# mini-v1_8-seed.net
KiCad netlist of a schematic drawn in EAGLE
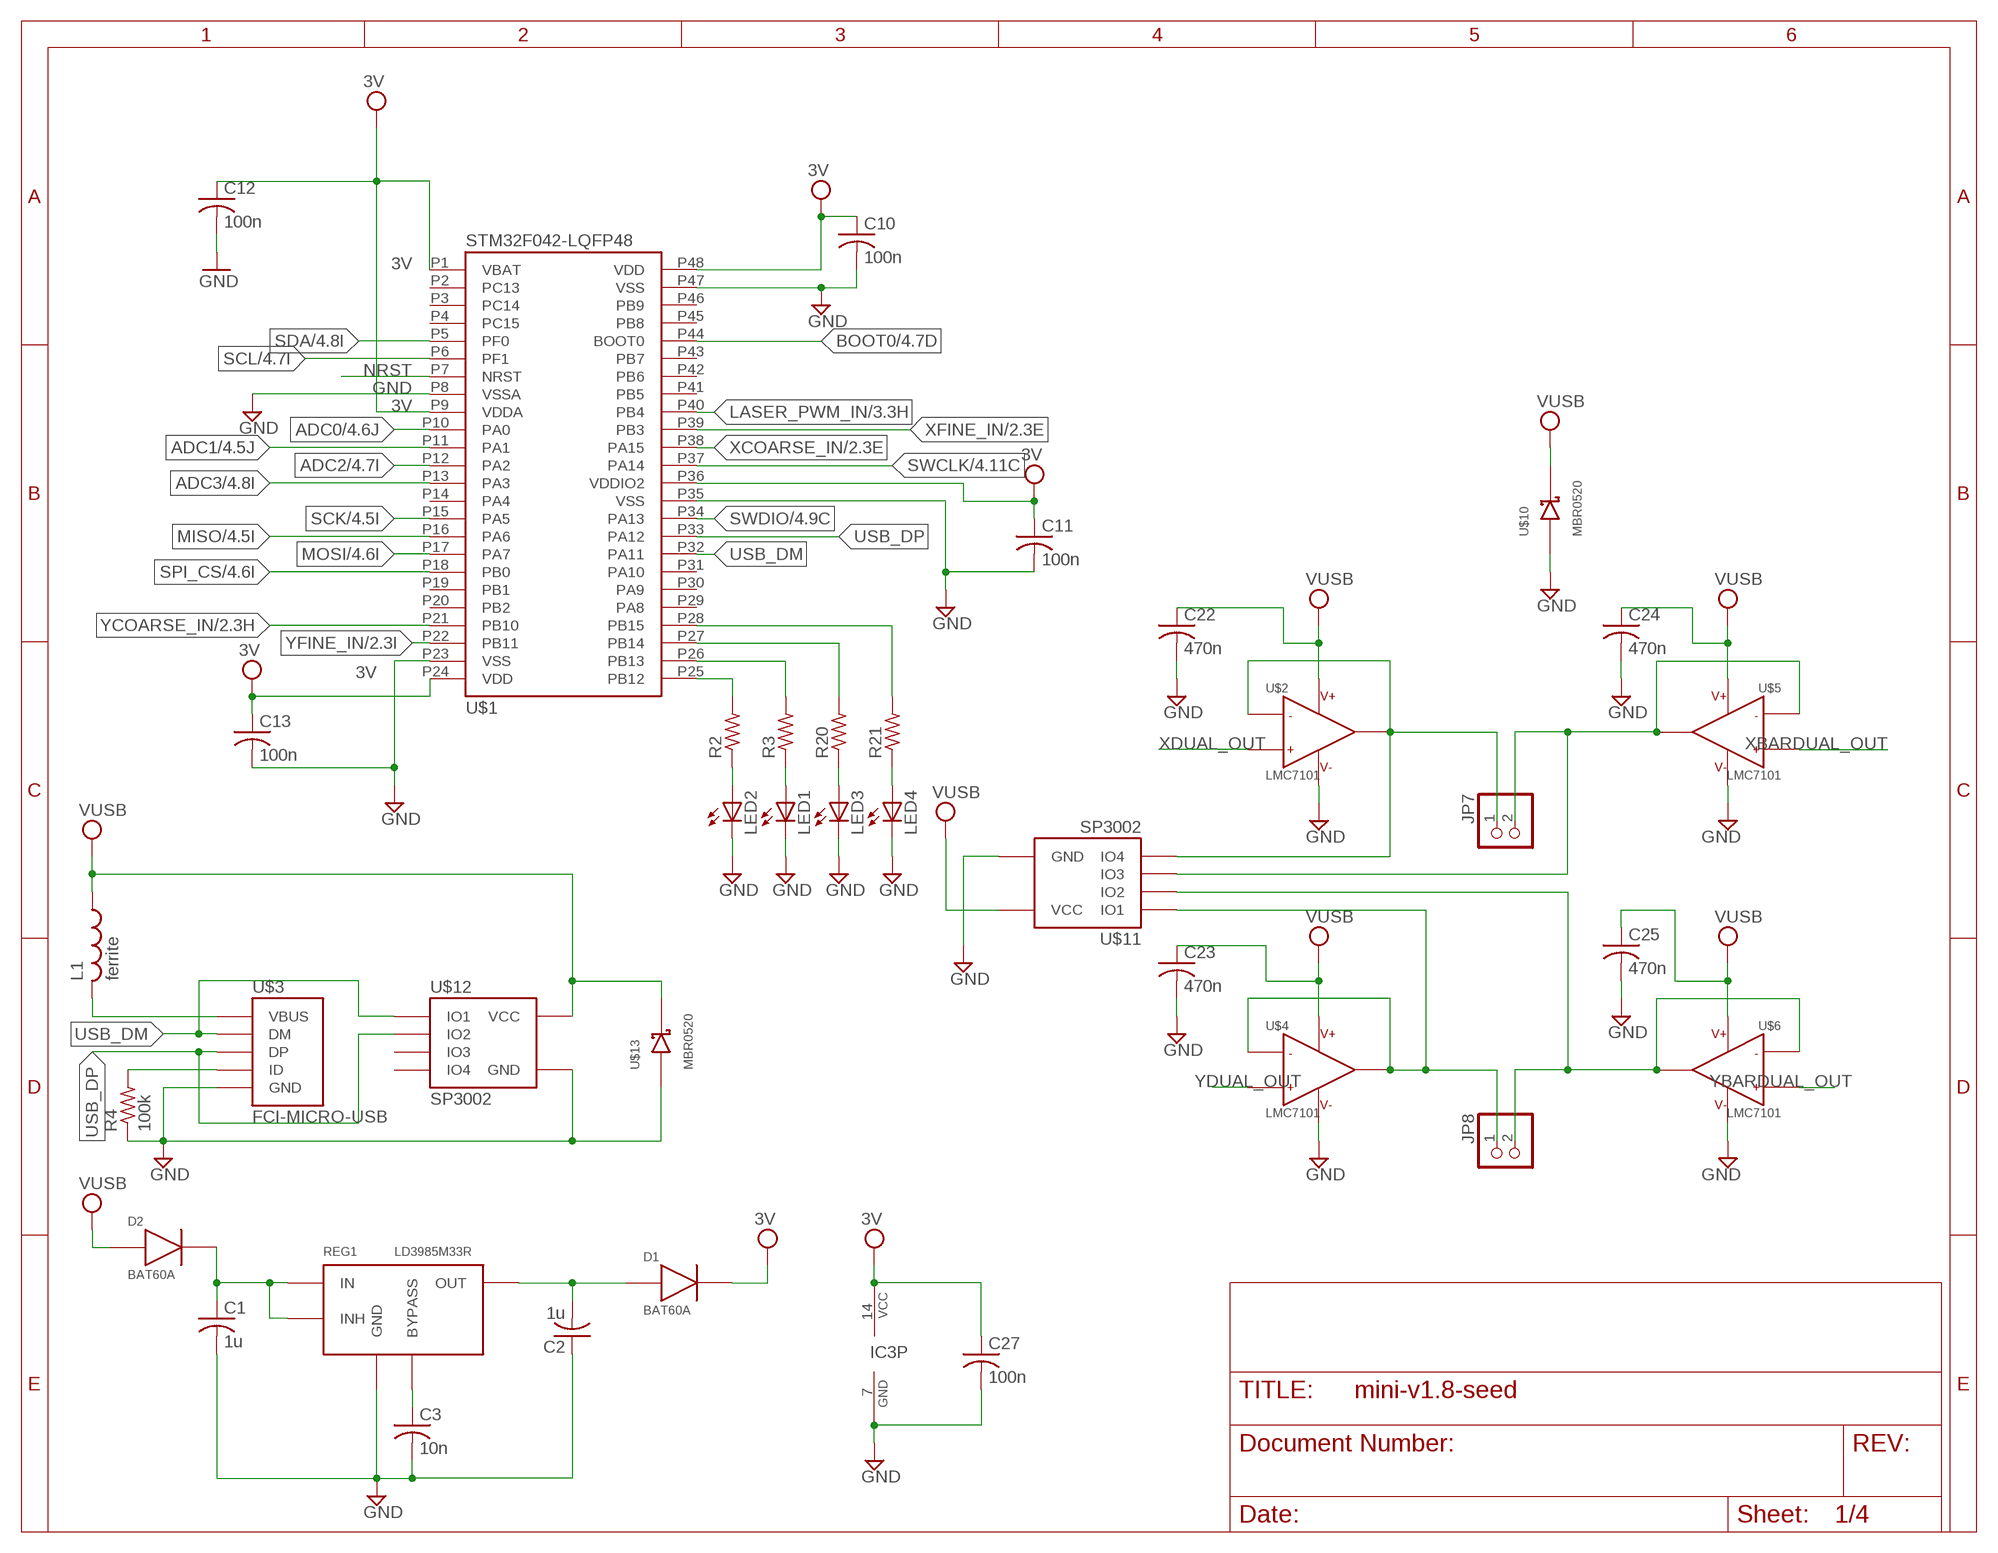
[diagram p0: schematic, sheet 1]
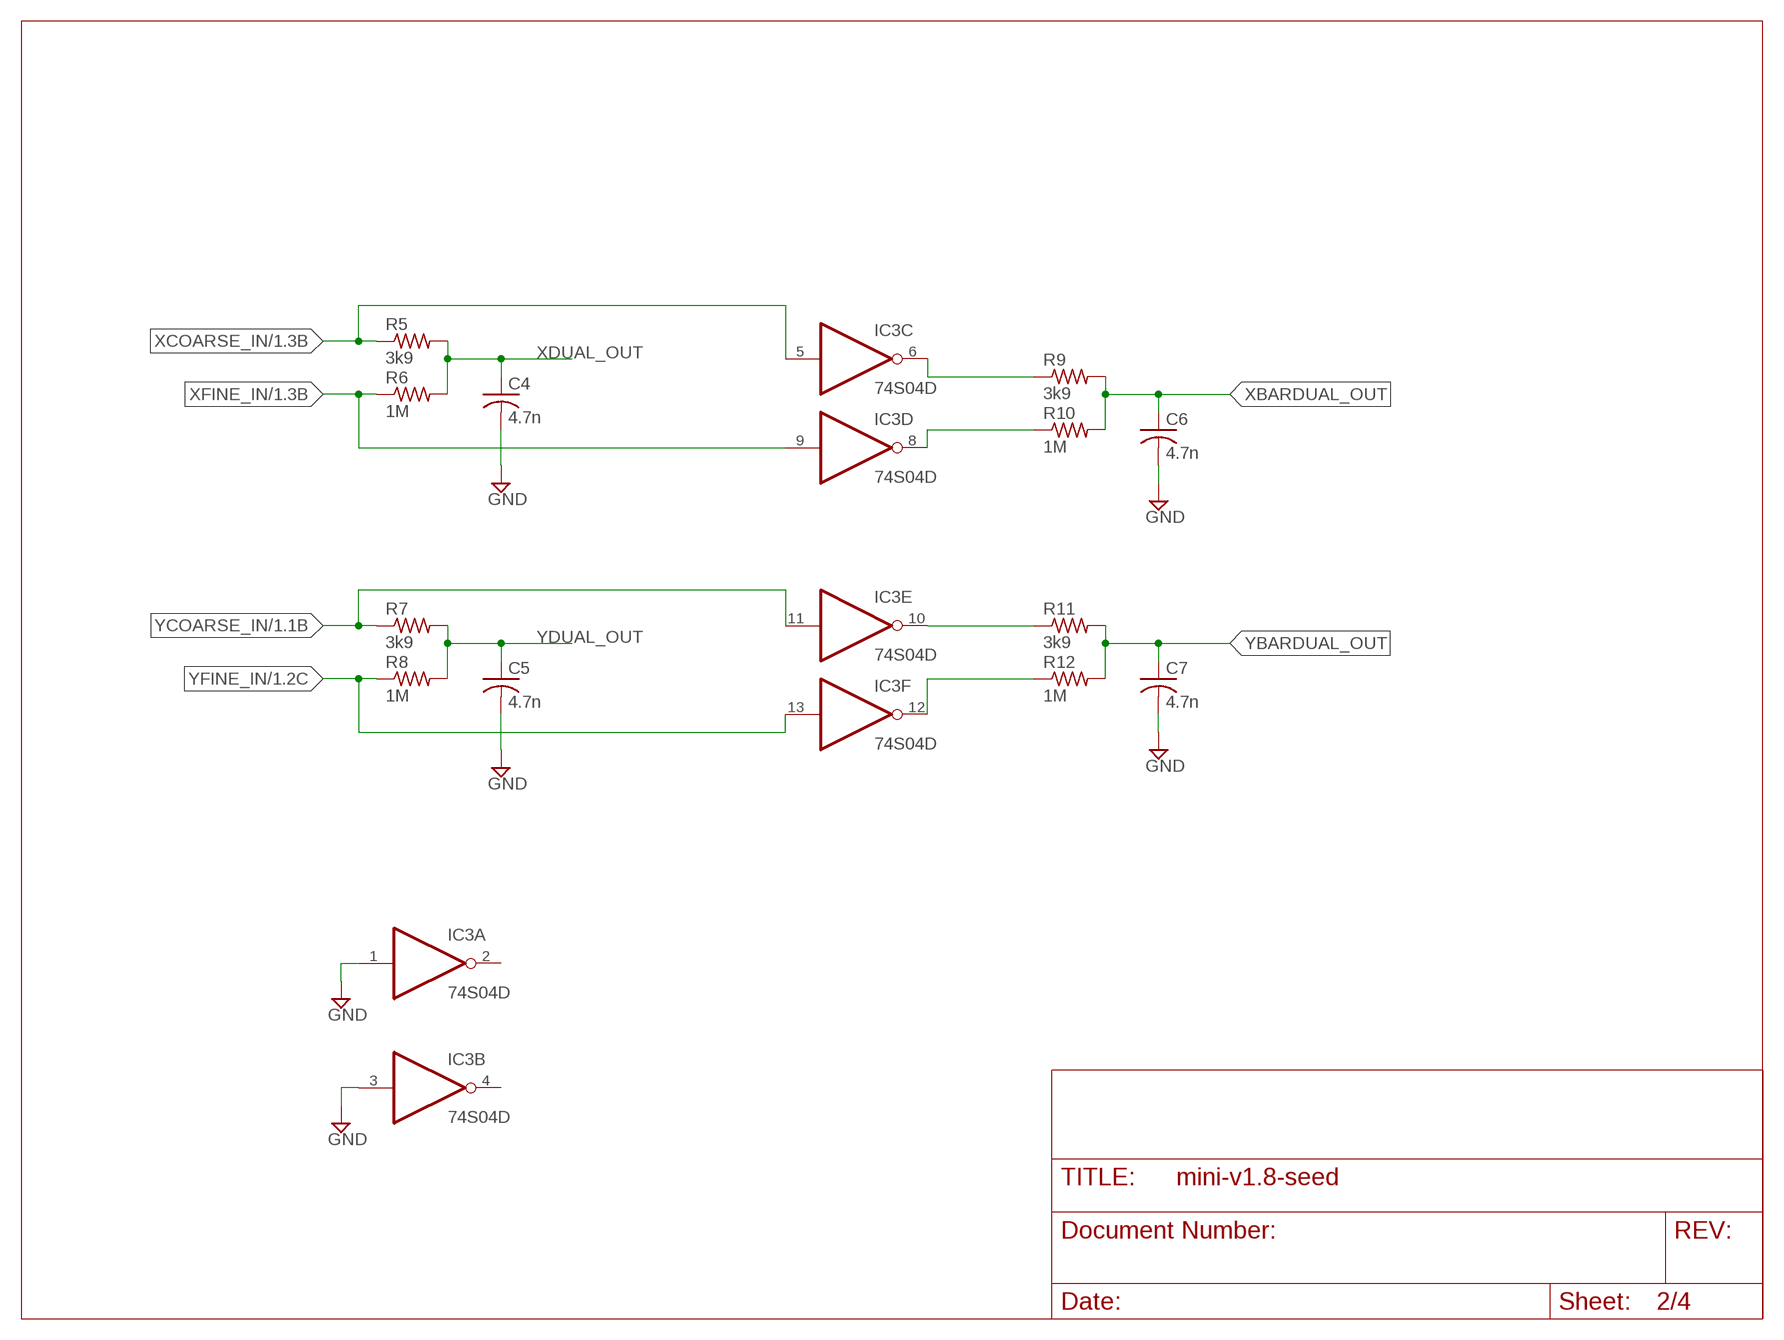
[diagram p1: schematic, sheet 2]
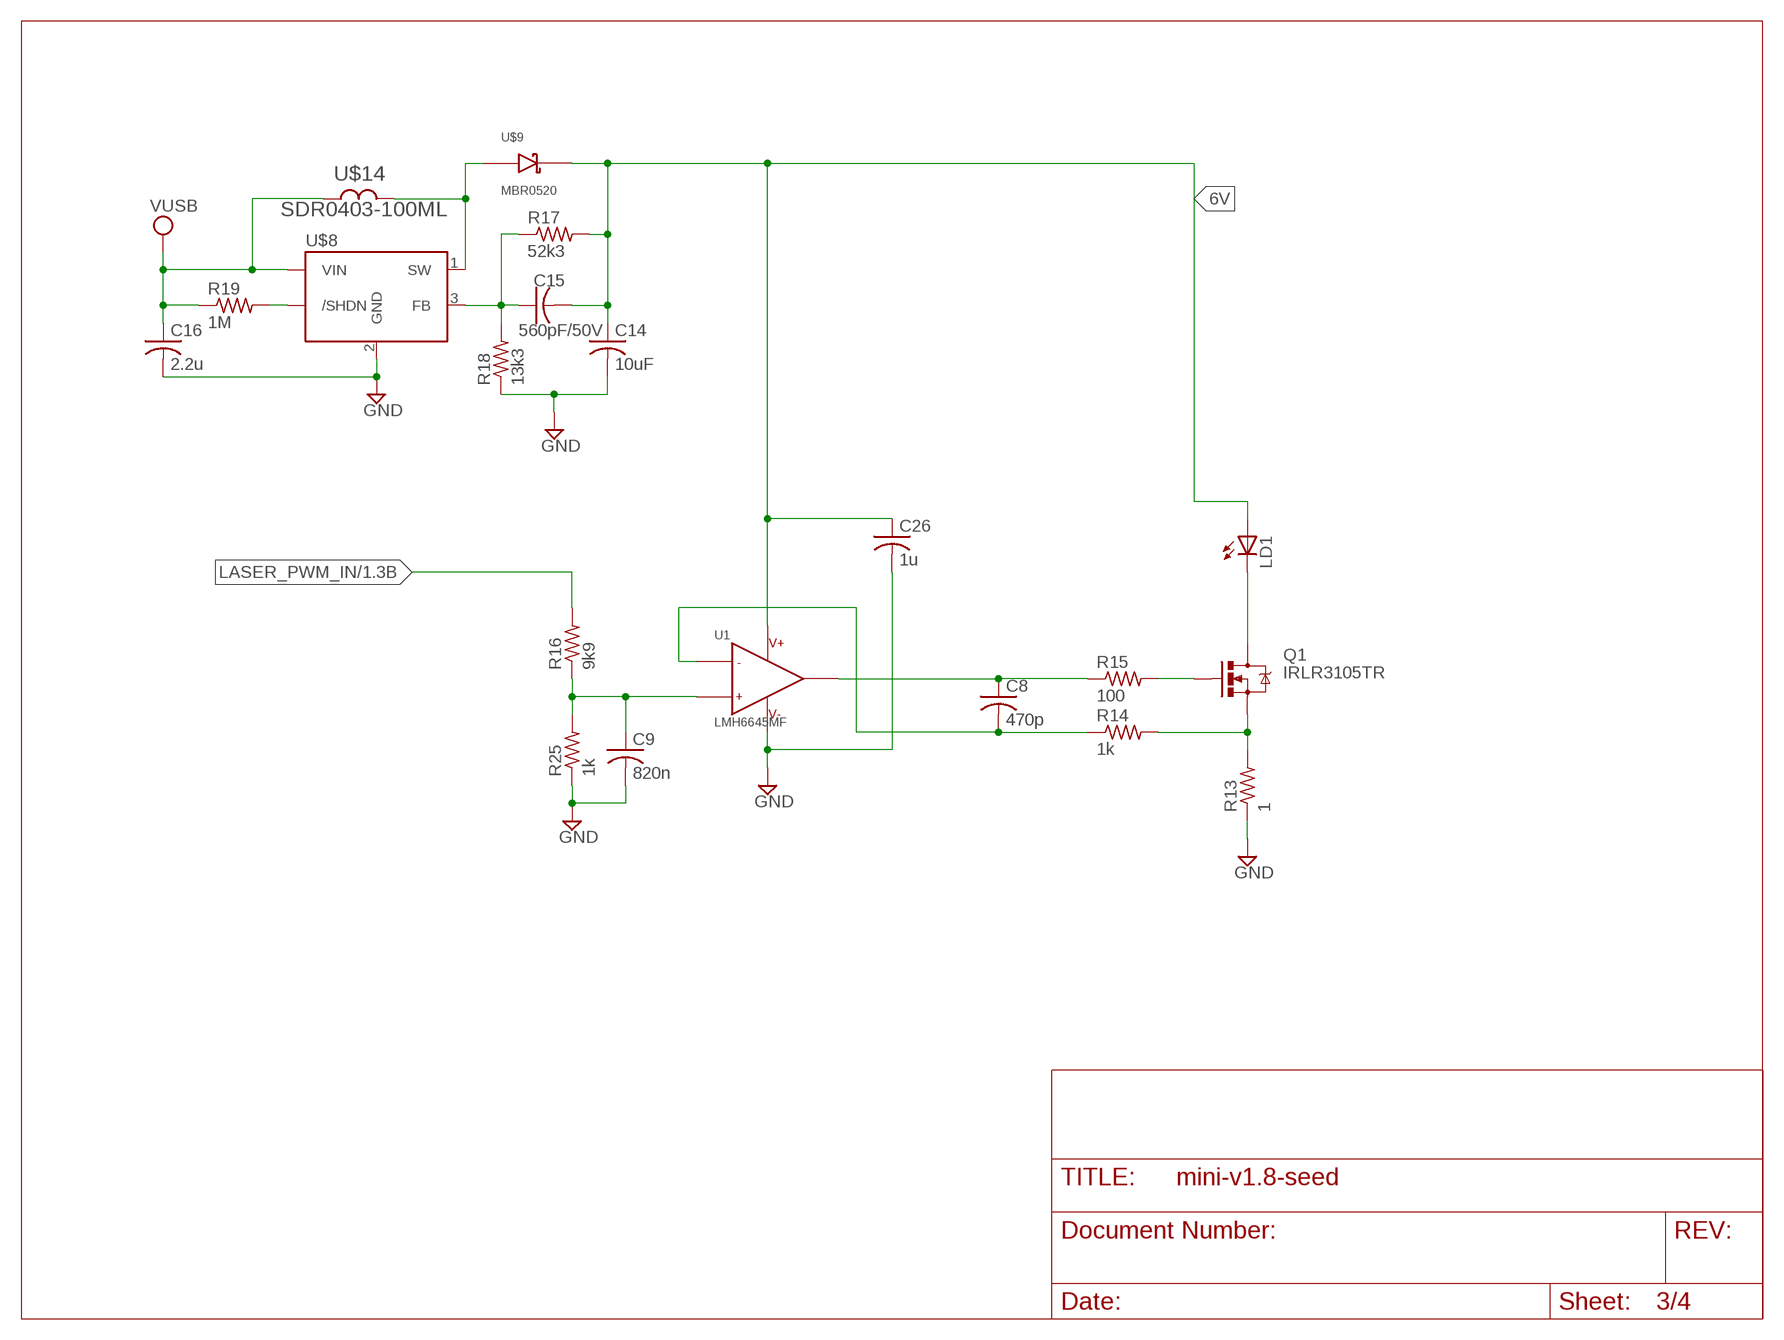
[diagram p2: schematic, sheet 3]
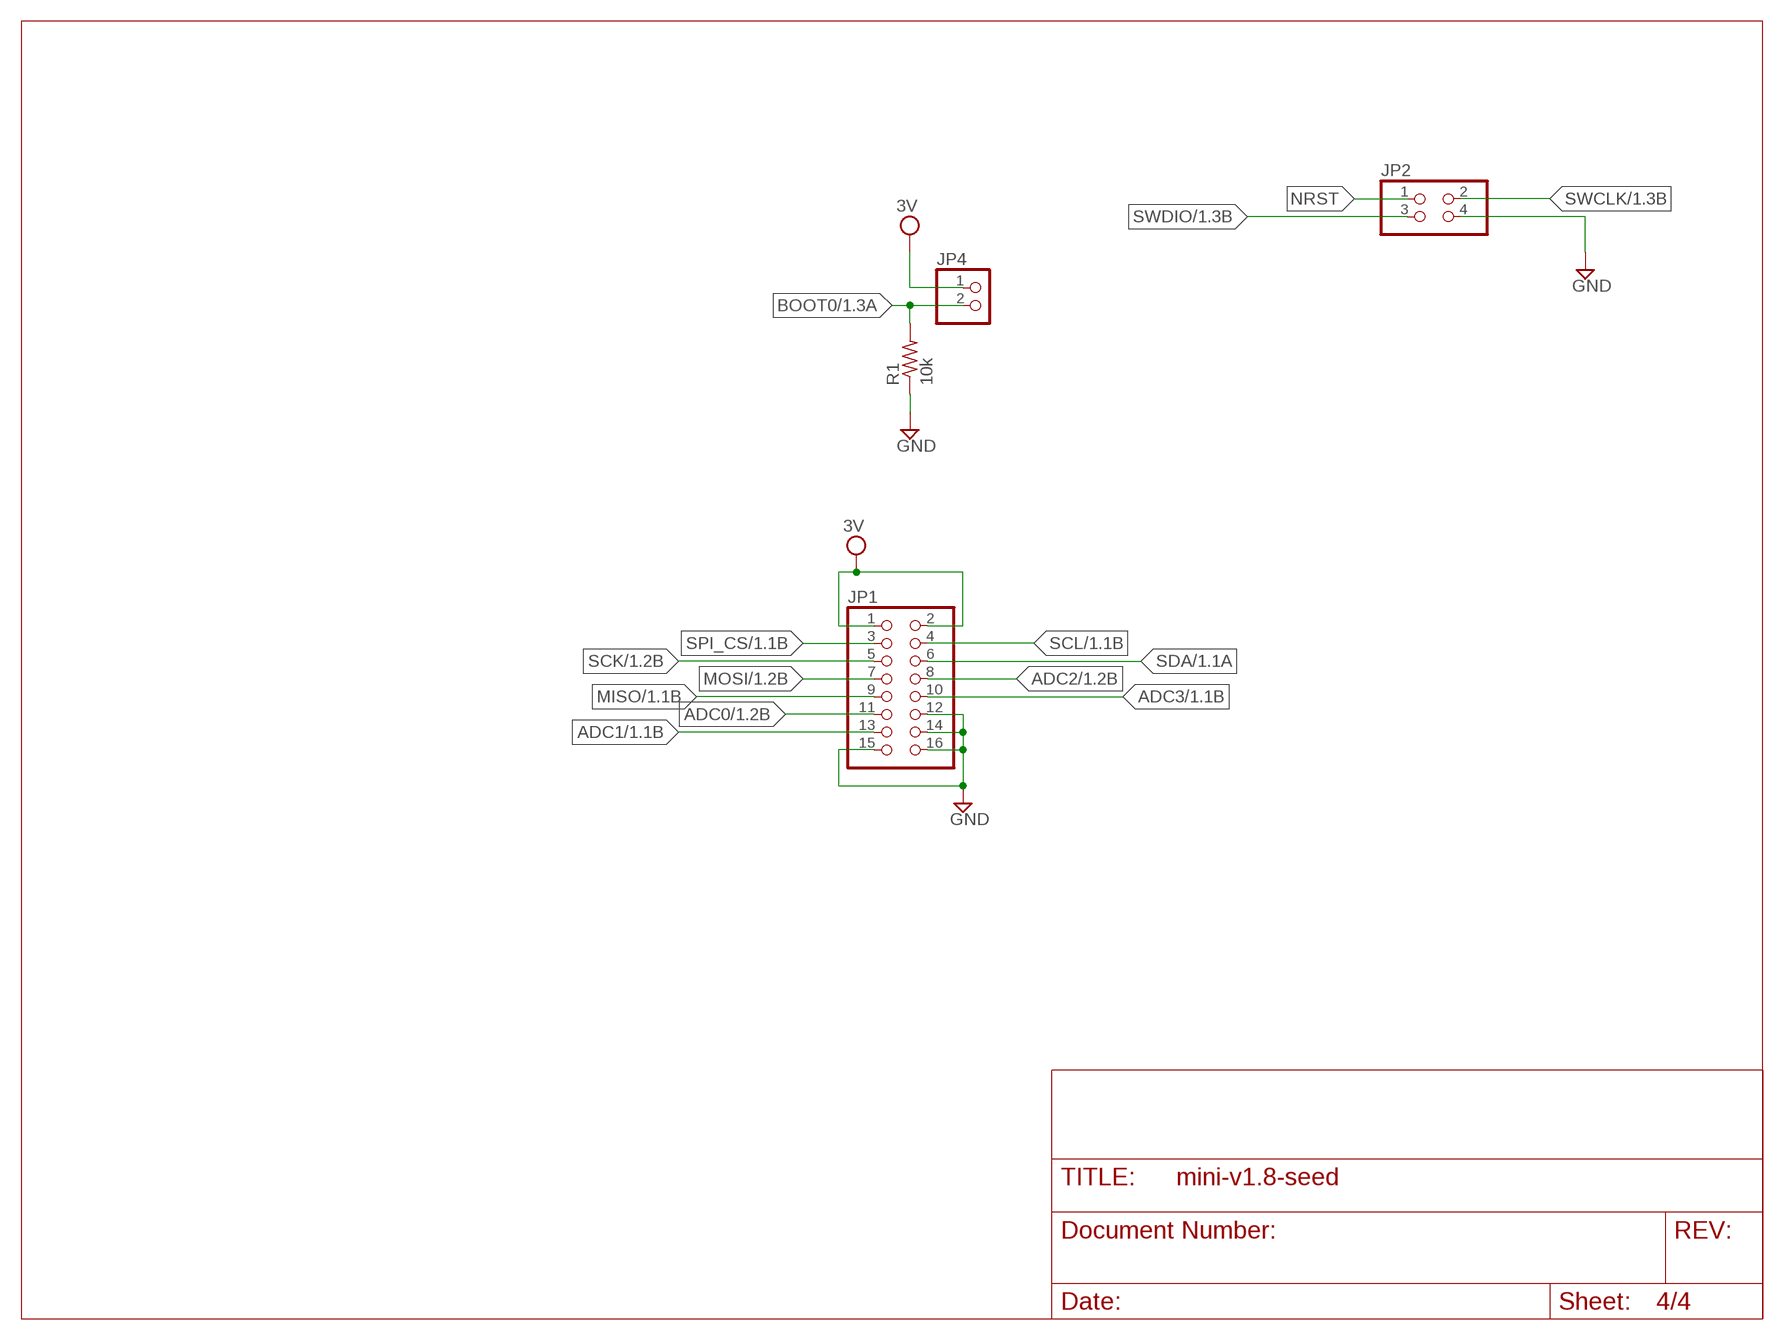
[diagram p3: schematic, sheet 4]

(export (version "E")
  (design (tool "Eeschema 10.0.6"))
  (components
    (comp (ref "C4")
      (value "4.7n")
      (footprint "eagle-import:C0603")
      (libsource (lib "eagle-import") (part "C-USC0603"))
    )
    (comp (ref "C5")
      (value "4.7n")
      (footprint "eagle-import:C0603")
      (libsource (lib "eagle-import") (part "C-USC0603"))
    )
    (comp (ref "C6")
      (value "4.7n")
      (footprint "eagle-import:C0603")
      (libsource (lib "eagle-import") (part "C-USC0603"))
    )
    (comp (ref "C7")
      (value "4.7n")
      (footprint "eagle-import:C0603")
      (libsource (lib "eagle-import") (part "C-USC0603"))
    )
    (comp (ref "IC3")
      (value "74S04D")
      (footprint "eagle-import:SO14")
      (libsource (lib "eagle-import") (part "7404DS"))
    )
    (comp (ref "R5")
      (value "3k9")
      (footprint "eagle-import:R0603")
      (libsource (lib "eagle-import") (part "R-US_R0603"))
    )
    (comp (ref "R6")
      (value "1M")
      (footprint "eagle-import:R0603")
      (libsource (lib "eagle-import") (part "R-US_R0603"))
    )
    (comp (ref "R7")
      (value "3k9")
      (footprint "eagle-import:R0603")
      (libsource (lib "eagle-import") (part "R-US_R0603"))
    )
    (comp (ref "R8")
      (value "1M")
      (footprint "eagle-import:R0603")
      (libsource (lib "eagle-import") (part "R-US_R0603"))
    )
    (comp (ref "R9")
      (value "3k9")
      (footprint "eagle-import:R0603")
      (libsource (lib "eagle-import") (part "R-US_R0603"))
    )
    (comp (ref "R10")
      (value "1M")
      (footprint "eagle-import:R0603")
      (libsource (lib "eagle-import") (part "R-US_R0603"))
    )
    (comp (ref "R11")
      (value "3k9")
      (footprint "eagle-import:R0603")
      (libsource (lib "eagle-import") (part "R-US_R0603"))
    )
    (comp (ref "R12")
      (value "1M")
      (footprint "eagle-import:R0603")
      (libsource (lib "eagle-import") (part "R-US_R0603"))
    )
    (comp (ref "C1")
      (value "1u")
      (footprint "eagle-import:C0603")
      (libsource (lib "eagle-import") (part "C-USC0603"))
    )
    (comp (ref "C2")
      (value "1u")
      (footprint "eagle-import:C0603")
      (libsource (lib "eagle-import") (part "C-USC0603"))
    )
    (comp (ref "C3")
      (value "10n")
      (footprint "eagle-import:C0603")
      (libsource (lib "eagle-import") (part "C-USC0603"))
    )
    (comp (ref "C10")
      (value "100n")
      (footprint "eagle-import:C0603")
      (libsource (lib "eagle-import") (part "C-USC0603"))
    )
    (comp (ref "C11")
      (value "100n")
      (footprint "eagle-import:C0603")
      (libsource (lib "eagle-import") (part "C-USC0603"))
    )
    (comp (ref "C12")
      (value "100n")
      (footprint "eagle-import:C0603")
      (libsource (lib "eagle-import") (part "C-USC0603"))
    )
    (comp (ref "C13")
      (value "100n")
      (footprint "eagle-import:C0603")
      (libsource (lib "eagle-import") (part "C-USC0603"))
    )
    (comp (ref "C22")
      (value "470n")
      (footprint "eagle-import:C0603")
      (libsource (lib "eagle-import") (part "C-USC0603"))
    )
    (comp (ref "C23")
      (value "470n")
      (footprint "eagle-import:C0603")
      (libsource (lib "eagle-import") (part "C-USC0603"))
    )
    (comp (ref "C24")
      (value "470n")
      (footprint "eagle-import:C0603")
      (libsource (lib "eagle-import") (part "C-USC0603"))
    )
    (comp (ref "C25")
      (value "470n")
      (footprint "eagle-import:C0603")
      (libsource (lib "eagle-import") (part "C-USC0603"))
    )
    (comp (ref "C27")
      (value "100n")
      (footprint "eagle-import:C0603")
      (libsource (lib "eagle-import") (part "C-USC0603"))
    )
    (comp (ref "D1")
      (value "BAT60A")
      (footprint "eagle-import:SOD323")
      (libsource (lib "eagle-import") (part "BAT60A"))
    )
    (comp (ref "D2")
      (value "BAT60A")
      (footprint "eagle-import:SOD323")
      (libsource (lib "eagle-import") (part "BAT60A"))
    )
    (comp (ref "JP7")
      (value "PINHD-1X2")
      (footprint "eagle-import:1X02")
      (libsource (lib "eagle-import") (part "PINHD-1X2"))
    )
    (comp (ref "JP8")
      (value "PINHD-1X2")
      (footprint "eagle-import:1X02")
      (libsource (lib "eagle-import") (part "PINHD-1X2"))
    )
    (comp (ref "L1")
      (value "ferrite")
      (footprint "eagle-import:C0603")
      (libsource (lib "eagle-import") (part "L-US"))
    )
    (comp (ref "LED1")
      (value "LEDCHIP-LED0603")
      (footprint "eagle-import:CHIP-LED0603")
      (libsource (lib "eagle-import") (part "LEDCHIP-LED0603"))
    )
    (comp (ref "LED2")
      (value "LEDCHIP-LED0603")
      (footprint "eagle-import:CHIP-LED0603")
      (libsource (lib "eagle-import") (part "LEDCHIP-LED0603"))
    )
    (comp (ref "LED3")
      (value "LEDCHIP-LED0603")
      (footprint "eagle-import:CHIP-LED0603")
      (libsource (lib "eagle-import") (part "LEDCHIP-LED0603"))
    )
    (comp (ref "LED4")
      (value "LEDCHIP-LED0603")
      (footprint "eagle-import:CHIP-LED0603")
      (libsource (lib "eagle-import") (part "LEDCHIP-LED0603"))
    )
    (comp (ref "R2")
      (value "R-US_R0603")
      (footprint "eagle-import:R0603")
      (libsource (lib "eagle-import") (part "R-US_R0603"))
    )
    (comp (ref "R3")
      (value "R-US_R0603")
      (footprint "eagle-import:R0603")
      (libsource (lib "eagle-import") (part "R-US_R0603"))
    )
    (comp (ref "R4")
      (value "100k")
      (footprint "eagle-import:R0603")
      (libsource (lib "eagle-import") (part "R-US_R0603"))
    )
    (comp (ref "R20")
      (value "R-US_R0603")
      (footprint "eagle-import:R0603")
      (libsource (lib "eagle-import") (part "R-US_R0603"))
    )
    (comp (ref "R21")
      (value "R-US_R0603")
      (footprint "eagle-import:R0603")
      (libsource (lib "eagle-import") (part "R-US_R0603"))
    )
    (comp (ref "REG1")
      (value "LD3985M33R")
      (footprint "eagle-import:SOT23-5L")
      (libsource (lib "eagle-import") (part "LD3985MXXR"))
    )
    (comp (ref "U$1")
      (value "STM32F042-LQFP48")
      (footprint "eagle-import:LQFP48")
      (libsource (lib "eagle-import") (part "STM32F042-LQFP48"))
    )
    (comp (ref "U$2")
      (value "LMC7101")
      (footprint "eagle-import:SOT23-5")
      (libsource (lib "eagle-import") (part "LMC7101"))
    )
    (comp (ref "U$3")
      (value "FCI-MICRO-USB")
      (footprint "eagle-import:FCI-MICROUSB")
      (libsource (lib "eagle-import") (part "FCI-MICRO-USB"))
    )
    (comp (ref "U$4")
      (value "LMC7101")
      (footprint "eagle-import:SOT23-5")
      (libsource (lib "eagle-import") (part "LMC7101"))
    )
    (comp (ref "U$5")
      (value "LMC7101")
      (footprint "eagle-import:SOT23-5")
      (libsource (lib "eagle-import") (part "LMC7101"))
    )
    (comp (ref "U$6")
      (value "LMC7101")
      (footprint "eagle-import:SOT23-5")
      (libsource (lib "eagle-import") (part "LMC7101"))
    )
    (comp (ref "U$10")
      (value "MBR0520")
      (footprint "eagle-import:SOD123")
      (libsource (lib "eagle-import") (part "MBR0520"))
    )
    (comp (ref "U$11")
      (value "SP3002")
      (footprint "eagle-import:SC70-6")
      (libsource (lib "eagle-import") (part "SP3002"))
    )
    (comp (ref "U$12")
      (value "SP3002")
      (footprint "eagle-import:SC70-6")
      (libsource (lib "eagle-import") (part "SP3002"))
    )
    (comp (ref "U$13")
      (value "MBR0520")
      (footprint "eagle-import:SOD123")
      (libsource (lib "eagle-import") (part "MBR0520"))
    )
    (comp (ref "C8")
      (value "470p")
      (footprint "eagle-import:C0603")
      (libsource (lib "eagle-import") (part "C-USC0603"))
    )
    (comp (ref "C9")
      (value "820n")
      (footprint "eagle-import:C0603")
      (libsource (lib "eagle-import") (part "C-USC0603"))
    )
    (comp (ref "C14")
      (value "10uF")
      (footprint "eagle-import:C0603")
      (libsource (lib "eagle-import") (part "C-USC0603"))
    )
    (comp (ref "C15")
      (value "560pF/50V")
      (footprint "eagle-import:C0603")
      (libsource (lib "eagle-import") (part "C-USC0603"))
    )
    (comp (ref "C16")
      (value "2.2u")
      (footprint "eagle-import:C0603")
      (libsource (lib "eagle-import") (part "C-USC0603"))
    )
    (comp (ref "C26")
      (value "1u")
      (footprint "eagle-import:C0603")
      (libsource (lib "eagle-import") (part "C-USC0603"))
    )
    (comp (ref "LD1")
      (value "LASERDIODELD2")
      (footprint "eagle-import:LASERDIODE2")
      (fields (field (name "MPN") "3 x (0552-2-15-15-11-27-10-0)"))
      (libsource (lib "eagle-import") (part "LASERDIODELD2"))
    )
    (comp (ref "Q1")
      (value "IRLR3105TR")
      (footprint "eagle-import:DPAK")
      (libsource (lib "eagle-import") (part "FET-N-IRLR3105TRIRLR3105TR"))
    )
    (comp (ref "R13")
      (value "1")
      (footprint "eagle-import:R0603")
      (libsource (lib "eagle-import") (part "R-US_R0603"))
    )
    (comp (ref "R14")
      (value "1k")
      (footprint "eagle-import:R0603")
      (libsource (lib "eagle-import") (part "R-US_R0603"))
    )
    (comp (ref "R15")
      (value "100")
      (footprint "eagle-import:R0603")
      (libsource (lib "eagle-import") (part "R-US_R0603"))
    )
    (comp (ref "R16")
      (value "9k9")
      (footprint "eagle-import:R0603")
      (libsource (lib "eagle-import") (part "R-US_R0603"))
    )
    (comp (ref "R17")
      (value "52k3")
      (footprint "eagle-import:R0603")
      (libsource (lib "eagle-import") (part "R-US_R0603"))
    )
    (comp (ref "R18")
      (value "13k3")
      (footprint "eagle-import:R0603")
      (libsource (lib "eagle-import") (part "R-US_R0603"))
    )
    (comp (ref "R19")
      (value "1M")
      (footprint "eagle-import:R0603")
      (libsource (lib "eagle-import") (part "R-US_R0603"))
    )
    (comp (ref "R25")
      (value "1k")
      (footprint "eagle-import:R0603")
      (libsource (lib "eagle-import") (part "R-US_R0603"))
    )
    (comp (ref "U$8")
      (value "LMR62014")
      (footprint "eagle-import:SOT23-5")
      (libsource (lib "eagle-import") (part "LMR62014"))
    )
    (comp (ref "U$9")
      (value "MBR0520")
      (footprint "eagle-import:SOD123")
      (libsource (lib "eagle-import") (part "MBR0520"))
    )
    (comp (ref "U$14")
      (value "SDR0403-100ML")
      (footprint "eagle-import:SDR0403")
      (libsource (lib "eagle-import") (part "SDR0403"))
    )
    (comp (ref "U1")
      (value "LMH6645MF")
      (footprint "eagle-import:SOT23-5")
      (libsource (lib "eagle-import") (part "OPAMP-SINGLELMH6645MF"))
    )
    (comp (ref "JP1")
      (value "PINHD-2X8")
      (footprint "eagle-import:2X08")
      (libsource (lib "eagle-import") (part "PINHD-2X8"))
    )
    (comp (ref "JP2")
      (value "PINHD-2X2")
      (footprint "eagle-import:2X02")
      (libsource (lib "eagle-import") (part "PINHD-2X2"))
    )
    (comp (ref "JP4")
      (value "PINHD-1X2")
      (footprint "eagle-import:1X02")
      (libsource (lib "eagle-import") (part "PINHD-1X2"))
    )
    (comp (ref "R1")
      (value "10k")
      (footprint "eagle-import:R0603")
      (libsource (lib "eagle-import") (part "R-US_R0603"))
    )
  )
  (nets
    (net (code "1") (name "3V") (class "Default")
      (node (ref "C10") (pin "1") (pinfunction "1_1") (pintype "passive"))
      (node (ref "C11") (pin "1") (pinfunction "1_1") (pintype "passive"))
      (node (ref "C12") (pin "1") (pinfunction "1_1") (pintype "passive"))
      (node (ref "C13") (pin "1") (pinfunction "1_1") (pintype "passive"))
      (node (ref "C27") (pin "1") (pinfunction "1_1") (pintype "passive"))
      (node (ref "D1") (pin "1") (pinfunction "1_1") (pintype "bidirectional"))
      (node (ref "IC3") (pin "14") (pinfunction "VCC_14") (pintype "power_in"))
      (node (ref "JP1") (pin "1") (pinfunction "1_1") (pintype "passive"))
      (node (ref "JP1") (pin "2") (pinfunction "2_2") (pintype "passive"))
      (node (ref "JP4") (pin "1") (pinfunction "1_1") (pintype "passive"))
      (node (ref "U$1") (pin "P1") (pinfunction "VBAT_P1") (pintype "bidirectional"))
      (node (ref "U$1") (pin "P24") (pinfunction "VDD_P24") (pintype "bidirectional"))
      (node (ref "U$1") (pin "P36") (pinfunction "VDDIO2_P36") (pintype "bidirectional"))
      (node (ref "U$1") (pin "P48") (pinfunction "VDD_P48") (pintype "bidirectional"))
      (node (ref "U$1") (pin "P9") (pinfunction "VDDA_P9") (pintype "bidirectional"))
    )
    (net (code "2") (name "6V") (class "Default")
      (node (ref "C14") (pin "1") (pinfunction "1_1") (pintype "passive"))
      (node (ref "C15") (pin "2") (pinfunction "2_2") (pintype "passive"))
      (node (ref "C26") (pin "1") (pinfunction "1_1") (pintype "passive"))
      (node (ref "LD1") (pin "P$1") (pinfunction "A_P$1") (pintype "passive"))
      (node (ref "R17") (pin "2") (pinfunction "2_2") (pintype "passive"))
      (node (ref "U$9") (pin "CATHODE") (pinfunction "CATHODE_CATHODE") (pintype "bidirectional"))
      (node (ref "U1") (pin "5") (pinfunction "V+_5") (pintype "power_in"))
    )
    (net (code "3") (name "ADC0") (class "Default")
      (node (ref "JP1") (pin "11") (pinfunction "11_11") (pintype "passive"))
      (node (ref "U$1") (pin "P10") (pinfunction "PA0_P10") (pintype "bidirectional"))
    )
    (net (code "4") (name "ADC1") (class "Default")
      (node (ref "JP1") (pin "13") (pinfunction "13_13") (pintype "passive"))
      (node (ref "U$1") (pin "P11") (pinfunction "PA1_P11") (pintype "bidirectional"))
    )
    (net (code "5") (name "ADC2") (class "Default")
      (node (ref "JP1") (pin "8") (pinfunction "8_8") (pintype "passive"))
      (node (ref "U$1") (pin "P12") (pinfunction "PA2_P12") (pintype "bidirectional"))
    )
    (net (code "6") (name "ADC3") (class "Default")
      (node (ref "JP1") (pin "10") (pinfunction "10_10") (pintype "passive"))
      (node (ref "U$1") (pin "P13") (pinfunction "PA3_P13") (pintype "bidirectional"))
    )
    (net (code "7") (name "BOOT0") (class "Default")
      (node (ref "JP4") (pin "2") (pinfunction "2_2") (pintype "passive"))
      (node (ref "R1") (pin "2") (pinfunction "2_2") (pintype "passive"))
      (node (ref "U$1") (pin "P44") (pinfunction "BOOT0_P44") (pintype "bidirectional"))
    )
    (net (code "8") (name "GND") (class "Default")
      (node (ref "C1") (pin "2") (pinfunction "2_2") (pintype "passive"))
      (node (ref "C10") (pin "2") (pinfunction "2_2") (pintype "passive"))
      (node (ref "C11") (pin "2") (pinfunction "2_2") (pintype "passive"))
      (node (ref "C12") (pin "2") (pinfunction "2_2") (pintype "passive"))
      (node (ref "C13") (pin "2") (pinfunction "2_2") (pintype "passive"))
      (node (ref "C14") (pin "2") (pinfunction "2_2") (pintype "passive"))
      (node (ref "C16") (pin "2") (pinfunction "2_2") (pintype "passive"))
      (node (ref "C2") (pin "1") (pinfunction "1_1") (pintype "passive"))
      (node (ref "C22") (pin "2") (pinfunction "2_2") (pintype "passive"))
      (node (ref "C23") (pin "2") (pinfunction "2_2") (pintype "passive"))
      (node (ref "C24") (pin "2") (pinfunction "2_2") (pintype "passive"))
      (node (ref "C25") (pin "2") (pinfunction "2_2") (pintype "passive"))
      (node (ref "C26") (pin "2") (pinfunction "2_2") (pintype "passive"))
      (node (ref "C27") (pin "2") (pinfunction "2_2") (pintype "passive"))
      (node (ref "C3") (pin "2") (pinfunction "2_2") (pintype "passive"))
      (node (ref "C4") (pin "2") (pinfunction "2_2") (pintype "passive"))
      (node (ref "C5") (pin "2") (pinfunction "2_2") (pintype "passive"))
      (node (ref "C6") (pin "2") (pinfunction "2_2") (pintype "passive"))
      (node (ref "C7") (pin "2") (pinfunction "2_2") (pintype "passive"))
      (node (ref "C9") (pin "2") (pinfunction "2_2") (pintype "passive"))
      (node (ref "IC3") (pin "1") (pinfunction "I_1") (pintype "input"))
      (node (ref "IC3") (pin "3") (pinfunction "I_3") (pintype "input"))
      (node (ref "IC3") (pin "7") (pinfunction "GND_7") (pintype "power_in"))
      (node (ref "JP1") (pin "12") (pinfunction "12_12") (pintype "passive"))
      (node (ref "JP1") (pin "14") (pinfunction "14_14") (pintype "passive"))
      (node (ref "JP1") (pin "15") (pinfunction "15_15") (pintype "passive"))
      (node (ref "JP1") (pin "16") (pinfunction "16_16") (pintype "passive"))
      (node (ref "JP2") (pin "4") (pinfunction "4_4") (pintype "passive"))
      (node (ref "LED1") (pin "C") (pinfunction "C_C") (pintype "passive"))
      (node (ref "LED2") (pin "C") (pinfunction "C_C") (pintype "passive"))
      (node (ref "LED3") (pin "C") (pinfunction "C_C") (pintype "passive"))
      (node (ref "LED4") (pin "C") (pinfunction "C_C") (pintype "passive"))
      (node (ref "R1") (pin "1") (pinfunction "1_1") (pintype "passive"))
      (node (ref "R13") (pin "1") (pinfunction "1_1") (pintype "passive"))
      (node (ref "R18") (pin "1") (pinfunction "1_1") (pintype "passive"))
      (node (ref "R25") (pin "1") (pinfunction "1_1") (pintype "passive"))
      (node (ref "R4") (pin "1") (pinfunction "1_1") (pintype "passive"))
      (node (ref "REG1") (pin "GND") (pinfunction "GND_GND") (pintype "bidirectional"))
      (node (ref "U$1") (pin "P23") (pinfunction "VSS_P23") (pintype "bidirectional"))
      (node (ref "U$1") (pin "P35") (pinfunction "VSS_P35") (pintype "bidirectional"))
      (node (ref "U$1") (pin "P47") (pinfunction "VSS_P47") (pintype "bidirectional"))
      (node (ref "U$1") (pin "P8") (pinfunction "VSSA_P8") (pintype "bidirectional"))
      (node (ref "U$10") (pin "ANODE") (pinfunction "ANODE_ANODE") (pintype "bidirectional"))
      (node (ref "U$11") (pin "P2") (pinfunction "GND_P2") (pintype "power_in"))
      (node (ref "U$12") (pin "P2") (pinfunction "GND_P2") (pintype "power_in"))
      (node (ref "U$13") (pin "ANODE") (pinfunction "ANODE_ANODE") (pintype "bidirectional"))
      (node (ref "U$2") (pin "5") (pinfunction "P5_5") (pintype "power_in"))
      (node (ref "U$3") (pin "P5") (pinfunction "GND_P5") (pintype "bidirectional"))
      (node (ref "U$4") (pin "5") (pinfunction "P5_5") (pintype "power_in"))
      (node (ref "U$5") (pin "5") (pinfunction "P5_5") (pintype "power_in"))
      (node (ref "U$6") (pin "5") (pinfunction "P5_5") (pintype "power_in"))
      (node (ref "U$8") (pin "2") (pinfunction "GND_2") (pintype "bidirectional"))
      (node (ref "U1") (pin "2") (pinfunction "V-_2") (pintype "power_in"))
    )
    (net (code "9") (name "LASER_PWM_IN") (class "Default")
      (node (ref "R16") (pin "2") (pinfunction "2_2") (pintype "passive"))
      (node (ref "U$1") (pin "P40") (pinfunction "PB4_P40") (pintype "bidirectional"))
    )
    (net (code "10") (name "MISO") (class "Default")
      (node (ref "JP1") (pin "9") (pinfunction "9_9") (pintype "passive"))
      (node (ref "U$1") (pin "P16") (pinfunction "PA6_P16") (pintype "bidirectional"))
    )
    (net (code "11") (name "MOSI") (class "Default")
      (node (ref "JP1") (pin "7") (pinfunction "7_7") (pintype "passive"))
      (node (ref "U$1") (pin "P17") (pinfunction "PA7_P17") (pintype "bidirectional"))
    )
    (net (code "12") (name "NRST") (class "Default")
      (node (ref "JP2") (pin "1") (pinfunction "1_1") (pintype "passive"))
      (node (ref "U$1") (pin "P7") (pinfunction "NRST_P7") (pintype "bidirectional"))
    )
    (net (code "13") (name "Net-(C2-Pad2)") (class "Default")
      (node (ref "C2") (pin "2") (pinfunction "2_2") (pintype "passive"))
      (node (ref "D1") (pin "2") (pinfunction "2_2") (pintype "bidirectional"))
      (node (ref "REG1") (pin "OUT") (pinfunction "OUT_OUT") (pintype "bidirectional"))
    )
    (net (code "14") (name "Net-(C3-Pad1)") (class "Default")
      (node (ref "C3") (pin "1") (pinfunction "1_1") (pintype "passive"))
      (node (ref "REG1") (pin "BYPASS") (pinfunction "BYPASS_BYPASS") (pintype "bidirectional"))
    )
    (net (code "15") (name "Net-(IC3C-O)") (class "Default")
      (node (ref "IC3") (pin "6") (pinfunction "O_6") (pintype "output"))
      (node (ref "R9") (pin "1") (pinfunction "1_1") (pintype "passive"))
    )
    (net (code "16") (name "Net-(IC3D-O)") (class "Default")
      (node (ref "IC3") (pin "8") (pinfunction "O_8") (pintype "output"))
      (node (ref "R10") (pin "1") (pinfunction "1_1") (pintype "passive"))
    )
    (net (code "17") (name "Net-(IC3E-O)") (class "Default")
      (node (ref "IC3") (pin "10") (pinfunction "O_10") (pintype "output"))
      (node (ref "R11") (pin "1") (pinfunction "1_1") (pintype "passive"))
    )
    (net (code "18") (name "Net-(IC3F-O)") (class "Default")
      (node (ref "IC3") (pin "12") (pinfunction "O_12") (pintype "output"))
      (node (ref "R12") (pin "1") (pinfunction "1_1") (pintype "passive"))
    )
    (net (code "19") (name "Net-(LD1-C)") (class "Default")
      (node (ref "LD1") (pin "P$3") (pinfunction "C_P$3") (pintype "passive"))
      (node (ref "Q1") (pin "4") (pinfunction "D_4") (pintype "passive"))
    )
    (net (code "20") (name "Net-(LED1-PadA)") (class "Default")
      (node (ref "LED1") (pin "A") (pinfunction "A_A") (pintype "passive"))
      (node (ref "R3") (pin "1") (pinfunction "1_1") (pintype "passive"))
    )
    (net (code "21") (name "Net-(LED2-PadA)") (class "Default")
      (node (ref "LED2") (pin "A") (pinfunction "A_A") (pintype "passive"))
      (node (ref "R2") (pin "1") (pinfunction "1_1") (pintype "passive"))
    )
    (net (code "22") (name "Net-(LED3-PadA)") (class "Default")
      (node (ref "LED3") (pin "A") (pinfunction "A_A") (pintype "passive"))
      (node (ref "R20") (pin "1") (pinfunction "1_1") (pintype "passive"))
    )
    (net (code "23") (name "Net-(LED4-PadA)") (class "Default")
      (node (ref "LED4") (pin "A") (pinfunction "A_A") (pintype "passive"))
      (node (ref "R21") (pin "1") (pinfunction "1_1") (pintype "passive"))
    )
    (net (code "24") (name "Net-(Q1-G)") (class "Default")
      (node (ref "Q1") (pin "1") (pinfunction "G_1") (pintype "passive"))
      (node (ref "R15") (pin "2") (pinfunction "2_2") (pintype "passive"))
    )
    (net (code "25") (name "Net-(Q1-S)") (class "Default")
      (node (ref "Q1") (pin "3") (pinfunction "S_3") (pintype "passive"))
      (node (ref "R13") (pin "2") (pinfunction "2_2") (pintype "passive"))
      (node (ref "R14") (pin "2") (pinfunction "2_2") (pintype "passive"))
    )
    (net (code "26") (name "Net-(REG1-INH)") (class "Default")
      (node (ref "C1") (pin "1") (pinfunction "1_1") (pintype "passive"))
      (node (ref "D2") (pin "1") (pinfunction "1_1") (pintype "bidirectional"))
      (node (ref "REG1") (pin "IN") (pinfunction "IN_IN") (pintype "bidirectional"))
      (node (ref "REG1") (pin "INHIBIT") (pinfunction "INH_INHIBIT") (pintype "bidirectional"))
    )
    (net (code "27") (name "Net-(U$1-PB12)") (class "Default")
      (node (ref "R2") (pin "2") (pinfunction "2_2") (pintype "passive"))
      (node (ref "U$1") (pin "P25") (pinfunction "PB12_P25") (pintype "bidirectional"))
    )
    (net (code "28") (name "Net-(U$1-PB13)") (class "Default")
      (node (ref "R3") (pin "2") (pinfunction "2_2") (pintype "passive"))
      (node (ref "U$1") (pin "P26") (pinfunction "PB13_P26") (pintype "bidirectional"))
    )
    (net (code "29") (name "Net-(U$1-PB14)") (class "Default")
      (node (ref "R20") (pin "2") (pinfunction "2_2") (pintype "passive"))
      (node (ref "U$1") (pin "P27") (pinfunction "PB14_P27") (pintype "bidirectional"))
    )
    (net (code "30") (name "Net-(U$1-PB15)") (class "Default")
      (node (ref "R21") (pin "2") (pinfunction "2_2") (pintype "passive"))
      (node (ref "U$1") (pin "P28") (pinfunction "PB15_P28") (pintype "bidirectional"))
    )
    (net (code "31") (name "Net-(U$3-ID)") (class "Default")
      (node (ref "R4") (pin "2") (pinfunction "2_2") (pintype "passive"))
      (node (ref "U$3") (pin "P4") (pinfunction "ID_P4") (pintype "bidirectional"))
    )
    (net (code "32") (name "Net-(U$3-VBUS)") (class "Default")
      (node (ref "L1") (pin "2") (pinfunction "2_2") (pintype "passive"))
      (node (ref "U$3") (pin "P1") (pinfunction "VBUS_P1") (pintype "bidirectional"))
    )
    (net (code "33") (name "Net-(U$8-FB)") (class "Default")
      (node (ref "C15") (pin "1") (pinfunction "1_1") (pintype "passive"))
      (node (ref "R17") (pin "1") (pinfunction "1_1") (pintype "passive"))
      (node (ref "R18") (pin "2") (pinfunction "2_2") (pintype "passive"))
      (node (ref "U$8") (pin "3") (pinfunction "FB_3") (pintype "bidirectional"))
    )
    (net (code "34") (name "Net-(U$8-SW)") (class "Default")
      (node (ref "U$14") (pin "P$2") (pinfunction "P$2_P$2") (pintype "bidirectional"))
      (node (ref "U$8") (pin "1") (pinfunction "SW_1") (pintype "bidirectional"))
      (node (ref "U$9") (pin "ANODE") (pinfunction "ANODE_ANODE") (pintype "bidirectional"))
    )
    (net (code "35") (name "Net-(U$8-{slash}SHDN)") (class "Default")
      (node (ref "R19") (pin "2") (pinfunction "2_2") (pintype "passive"))
      (node (ref "U$8") (pin "4") (pinfunction "/SHDN_4") (pintype "bidirectional"))
    )
    (net (code "36") (name "Net-(U$11-IO1)") (class "Default")
      (node (ref "JP8") (pin "1") (pinfunction "1_1") (pintype "passive"))
      (node (ref "U$11") (pin "P1") (pinfunction "IO1_P1") (pintype "bidirectional"))
      (node (ref "U$4") (pin "1") (pinfunction "P1_1") (pintype "bidirectional"))
      (node (ref "U$4") (pin "4") (pinfunction "P4_4") (pintype "bidirectional"))
    )
    (net (code "37") (name "Net-(U$11-IO2)") (class "Default")
      (node (ref "JP8") (pin "2") (pinfunction "2_2") (pintype "passive"))
      (node (ref "U$11") (pin "P3") (pinfunction "IO2_P3") (pintype "bidirectional"))
      (node (ref "U$6") (pin "1") (pinfunction "P1_1") (pintype "bidirectional"))
      (node (ref "U$6") (pin "4") (pinfunction "P4_4") (pintype "bidirectional"))
    )
    (net (code "38") (name "Net-(U$11-IO3)") (class "Default")
      (node (ref "JP7") (pin "2") (pinfunction "2_2") (pintype "passive"))
      (node (ref "U$11") (pin "P4") (pinfunction "IO3_P4") (pintype "bidirectional"))
      (node (ref "U$5") (pin "1") (pinfunction "P1_1") (pintype "bidirectional"))
      (node (ref "U$5") (pin "4") (pinfunction "P4_4") (pintype "bidirectional"))
    )
    (net (code "39") (name "Net-(U$11-IO4)") (class "Default")
      (node (ref "JP7") (pin "1") (pinfunction "1_1") (pintype "passive"))
      (node (ref "U$11") (pin "P6") (pinfunction "IO4_P6") (pintype "bidirectional"))
      (node (ref "U$2") (pin "1") (pinfunction "P1_1") (pintype "bidirectional"))
      (node (ref "U$2") (pin "4") (pinfunction "P4_4") (pintype "bidirectional"))
    )
    (net (code "40") (name "Net-(U1-IN+)") (class "Default")
      (node (ref "C9") (pin "1") (pinfunction "1_1") (pintype "passive"))
      (node (ref "R16") (pin "1") (pinfunction "1_1") (pintype "passive"))
      (node (ref "R25") (pin "2") (pinfunction "2_2") (pintype "passive"))
      (node (ref "U1") (pin "3") (pinfunction "IN+_3") (pintype "bidirectional"))
    )
    (net (code "41") (name "Net-(U1-IN-)") (class "Default")
      (node (ref "C8") (pin "2") (pinfunction "2_2") (pintype "passive"))
      (node (ref "R14") (pin "1") (pinfunction "1_1") (pintype "passive"))
      (node (ref "U1") (pin "4") (pinfunction "IN-_4") (pintype "bidirectional"))
    )
    (net (code "42") (name "Net-(U1-OUT)") (class "Default")
      (node (ref "C8") (pin "1") (pinfunction "1_1") (pintype "passive"))
      (node (ref "R15") (pin "1") (pinfunction "1_1") (pintype "passive"))
      (node (ref "U1") (pin "1") (pinfunction "OUT_1") (pintype "bidirectional"))
    )
    (net (code "43") (name "SCK") (class "Default")
      (node (ref "JP1") (pin "5") (pinfunction "5_5") (pintype "passive"))
      (node (ref "U$1") (pin "P15") (pinfunction "PA5_P15") (pintype "bidirectional"))
    )
    (net (code "44") (name "SCL") (class "Default")
      (node (ref "JP1") (pin "4") (pinfunction "4_4") (pintype "passive"))
      (node (ref "U$1") (pin "P6") (pinfunction "PF1_P6") (pintype "bidirectional"))
    )
    (net (code "45") (name "SDA") (class "Default")
      (node (ref "JP1") (pin "6") (pinfunction "6_6") (pintype "passive"))
      (node (ref "U$1") (pin "P5") (pinfunction "PF0_P5") (pintype "bidirectional"))
    )
    (net (code "46") (name "SPI_CS") (class "Default")
      (node (ref "JP1") (pin "3") (pinfunction "3_3") (pintype "passive"))
      (node (ref "U$1") (pin "P18") (pinfunction "PB0_P18") (pintype "bidirectional"))
    )
    (net (code "47") (name "SWCLK") (class "Default")
      (node (ref "JP2") (pin "2") (pinfunction "2_2") (pintype "passive"))
      (node (ref "U$1") (pin "P37") (pinfunction "PA14_P37") (pintype "bidirectional"))
    )
    (net (code "48") (name "SWDIO") (class "Default")
      (node (ref "JP2") (pin "3") (pinfunction "3_3") (pintype "passive"))
      (node (ref "U$1") (pin "P34") (pinfunction "PA13_P34") (pintype "bidirectional"))
    )
    (net (code "49") (name "USB_DM") (class "Default")
      (node (ref "U$1") (pin "P32") (pinfunction "PA11_P32") (pintype "bidirectional"))
      (node (ref "U$12") (pin "P1") (pinfunction "IO1_P1") (pintype "bidirectional"))
      (node (ref "U$3") (pin "P2") (pinfunction "DM_P2") (pintype "bidirectional"))
    )
    (net (code "50") (name "USB_DP") (class "Default")
      (node (ref "U$1") (pin "P33") (pinfunction "PA12_P33") (pintype "bidirectional"))
      (node (ref "U$12") (pin "P3") (pinfunction "IO2_P3") (pintype "bidirectional"))
      (node (ref "U$3") (pin "P3") (pinfunction "DP_P3") (pintype "bidirectional"))
    )
    (net (code "51") (name "VUSB") (class "Default")
      (node (ref "C16") (pin "1") (pinfunction "1_1") (pintype "passive"))
      (node (ref "C22") (pin "1") (pinfunction "1_1") (pintype "passive"))
      (node (ref "C23") (pin "1") (pinfunction "1_1") (pintype "passive"))
      (node (ref "C24") (pin "1") (pinfunction "1_1") (pintype "passive"))
      (node (ref "C25") (pin "1") (pinfunction "1_1") (pintype "passive"))
      (node (ref "D2") (pin "2") (pinfunction "2_2") (pintype "bidirectional"))
      (node (ref "L1") (pin "1") (pinfunction "1_1") (pintype "passive"))
      (node (ref "R19") (pin "1") (pinfunction "1_1") (pintype "passive"))
      (node (ref "U$10") (pin "CATHODE") (pinfunction "CATHODE_CATHODE") (pintype "bidirectional"))
      (node (ref "U$11") (pin "P5") (pinfunction "VCC_P5") (pintype "power_in"))
      (node (ref "U$12") (pin "P5") (pinfunction "VCC_P5") (pintype "power_in"))
      (node (ref "U$13") (pin "CATHODE") (pinfunction "CATHODE_CATHODE") (pintype "bidirectional"))
      (node (ref "U$14") (pin "P$1") (pinfunction "P$1_P$1") (pintype "bidirectional"))
      (node (ref "U$2") (pin "2") (pinfunction "P2_2") (pintype "power_in"))
      (node (ref "U$4") (pin "2") (pinfunction "P2_2") (pintype "power_in"))
      (node (ref "U$5") (pin "2") (pinfunction "P2_2") (pintype "power_in"))
      (node (ref "U$6") (pin "2") (pinfunction "P2_2") (pintype "power_in"))
      (node (ref "U$8") (pin "5") (pinfunction "VIN_5") (pintype "bidirectional"))
    )
    (net (code "52") (name "XBARDUAL_OUT") (class "Default")
      (node (ref "C6") (pin "1") (pinfunction "1_1") (pintype "passive"))
      (node (ref "R10") (pin "2") (pinfunction "2_2") (pintype "passive"))
      (node (ref "R9") (pin "2") (pinfunction "2_2") (pintype "passive"))
      (node (ref "U$5") (pin "3") (pinfunction "P3_3") (pintype "bidirectional"))
    )
    (net (code "53") (name "XCOARSE_IN") (class "Default")
      (node (ref "IC3") (pin "5") (pinfunction "I_5") (pintype "input"))
      (node (ref "R5") (pin "1") (pinfunction "1_1") (pintype "passive"))
      (node (ref "U$1") (pin "P38") (pinfunction "PA15_P38") (pintype "bidirectional"))
    )
    (net (code "54") (name "XDUAL_OUT") (class "Default")
      (node (ref "C4") (pin "1") (pinfunction "1_1") (pintype "passive"))
      (node (ref "R5") (pin "2") (pinfunction "2_2") (pintype "passive"))
      (node (ref "R6") (pin "2") (pinfunction "2_2") (pintype "passive"))
      (node (ref "U$2") (pin "3") (pinfunction "P3_3") (pintype "bidirectional"))
    )
    (net (code "55") (name "XFINE_IN") (class "Default")
      (node (ref "IC3") (pin "9") (pinfunction "I_9") (pintype "input"))
      (node (ref "R6") (pin "1") (pinfunction "1_1") (pintype "passive"))
      (node (ref "U$1") (pin "P39") (pinfunction "PB3_P39") (pintype "bidirectional"))
    )
    (net (code "56") (name "YBARDUAL_OUT") (class "Default")
      (node (ref "C7") (pin "1") (pinfunction "1_1") (pintype "passive"))
      (node (ref "R11") (pin "2") (pinfunction "2_2") (pintype "passive"))
      (node (ref "R12") (pin "2") (pinfunction "2_2") (pintype "passive"))
      (node (ref "U$6") (pin "3") (pinfunction "P3_3") (pintype "bidirectional"))
    )
    (net (code "57") (name "YCOARSE_IN") (class "Default")
      (node (ref "IC3") (pin "11") (pinfunction "I_11") (pintype "input"))
      (node (ref "R7") (pin "1") (pinfunction "1_1") (pintype "passive"))
      (node (ref "U$1") (pin "P21") (pinfunction "PB10_P21") (pintype "bidirectional"))
    )
    (net (code "58") (name "YDUAL_OUT") (class "Default")
      (node (ref "C5") (pin "1") (pinfunction "1_1") (pintype "passive"))
      (node (ref "R7") (pin "2") (pinfunction "2_2") (pintype "passive"))
      (node (ref "R8") (pin "2") (pinfunction "2_2") (pintype "passive"))
      (node (ref "U$4") (pin "3") (pinfunction "P3_3") (pintype "bidirectional"))
    )
    (net (code "59") (name "YFINE_IN") (class "Default")
      (node (ref "IC3") (pin "13") (pinfunction "I_13") (pintype "input"))
      (node (ref "R8") (pin "1") (pinfunction "1_1") (pintype "passive"))
      (node (ref "U$1") (pin "P22") (pinfunction "PB11_P22") (pintype "bidirectional"))
    )
    (net (code "60") (name "unconnected-(IC3A-O-Pad2)") (class "Default")
      (node (ref "IC3") (pin "2") (pinfunction "O_2") (pintype "output"))
    )
    (net (code "61") (name "unconnected-(IC3B-O-Pad4)") (class "Default")
      (node (ref "IC3") (pin "4") (pinfunction "O_4") (pintype "output"))
    )
    (net (code "62") (name "unconnected-(U$1-PA4-PadP14)") (class "Default")
      (node (ref "U$1") (pin "P14") (pinfunction "PA4_P14") (pintype "bidirectional"))
    )
    (net (code "63") (name "unconnected-(U$1-PA8-PadP29)") (class "Default")
      (node (ref "U$1") (pin "P29") (pinfunction "PA8_P29") (pintype "bidirectional"))
    )
    (net (code "64") (name "unconnected-(U$1-PA9-PadP30)") (class "Default")
      (node (ref "U$1") (pin "P30") (pinfunction "PA9_P30") (pintype "bidirectional"))
    )
    (net (code "65") (name "unconnected-(U$1-PA10-PadP31)") (class "Default")
      (node (ref "U$1") (pin "P31") (pinfunction "PA10_P31") (pintype "bidirectional"))
    )
    (net (code "66") (name "unconnected-(U$1-PB1-PadP19)") (class "Default")
      (node (ref "U$1") (pin "P19") (pinfunction "PB1_P19") (pintype "bidirectional"))
    )
    (net (code "67") (name "unconnected-(U$1-PB2-PadP20)") (class "Default")
      (node (ref "U$1") (pin "P20") (pinfunction "PB2_P20") (pintype "bidirectional"))
    )
    (net (code "68") (name "unconnected-(U$1-PB5-PadP41)") (class "Default")
      (node (ref "U$1") (pin "P41") (pinfunction "PB5_P41") (pintype "bidirectional"))
    )
    (net (code "69") (name "unconnected-(U$1-PB6-PadP42)") (class "Default")
      (node (ref "U$1") (pin "P42") (pinfunction "PB6_P42") (pintype "bidirectional"))
    )
    (net (code "70") (name "unconnected-(U$1-PB7-PadP43)") (class "Default")
      (node (ref "U$1") (pin "P43") (pinfunction "PB7_P43") (pintype "bidirectional"))
    )
    (net (code "71") (name "unconnected-(U$1-PB8-PadP45)") (class "Default")
      (node (ref "U$1") (pin "P45") (pinfunction "PB8_P45") (pintype "bidirectional"))
    )
    (net (code "72") (name "unconnected-(U$1-PB9-PadP46)") (class "Default")
      (node (ref "U$1") (pin "P46") (pinfunction "PB9_P46") (pintype "bidirectional"))
    )
    (net (code "73") (name "unconnected-(U$1-PC13-PadP2)") (class "Default")
      (node (ref "U$1") (pin "P2") (pinfunction "PC13_P2") (pintype "bidirectional"))
    )
    (net (code "74") (name "unconnected-(U$1-PC14-PadP3)") (class "Default")
      (node (ref "U$1") (pin "P3") (pinfunction "PC14_P3") (pintype "bidirectional"))
    )
    (net (code "75") (name "unconnected-(U$1-PC15-PadP4)") (class "Default")
      (node (ref "U$1") (pin "P4") (pinfunction "PC15_P4") (pintype "bidirectional"))
    )
    (net (code "76") (name "unconnected-(U$12-IO3-PadP4)") (class "Default")
      (node (ref "U$12") (pin "P4") (pinfunction "IO3_P4") (pintype "bidirectional"))
    )
    (net (code "77") (name "unconnected-(U$12-IO4-PadP6)") (class "Default")
      (node (ref "U$12") (pin "P6") (pinfunction "IO4_P6") (pintype "bidirectional"))
    )
  )
)
